# Coordinator.net
KiCad netlist of a schematic drawn in EAGLE
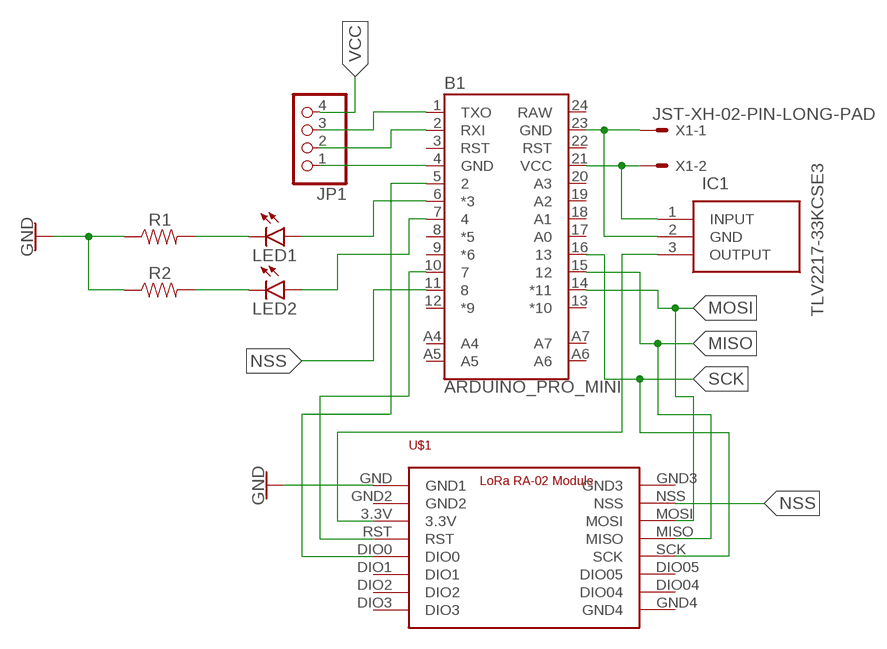
[diagram p0: schematic, sheet 1]

(export (version "E")
  (design (tool "Eeschema 10.0.6"))
  (components
    (comp (ref "B1")
      (value "ARDUINO_PRO_MINI")
      (footprint "eagle-import:ARDUINO_PRO_MINI")
      (libsource (lib "eagle-import") (part "ARDUINO_PRO_MINI"))
    )
    (comp (ref "IC1")
      (value "TLV2217-33KCSE3")
      (footprint "eagle-import:TO254P470X1016X1965-3P")
      (fields (field (name "MOUSER_PART_NUMBER") "595-TLV2217-33KCSE3"))
      (libsource (lib "eagle-import") (part "TLV2217-33KCSE3"))
    )
    (comp (ref "JP1")
      (value "PINHD-1X4")
      (footprint "eagle-import:1X04")
      (libsource (lib "eagle-import") (part "PINHD-1X4"))
    )
    (comp (ref "LED1")
      (value "LEDCHIPLED_0805")
      (footprint "eagle-import:CHIPLED_0805")
      (libsource (lib "eagle-import") (part "LEDCHIPLED_0805"))
    )
    (comp (ref "LED2")
      (value "LEDCHIPLED_0805")
      (footprint "eagle-import:CHIPLED_0805")
      (libsource (lib "eagle-import") (part "LEDCHIPLED_0805"))
    )
    (comp (ref "R1")
      (value "RESISTOR0805")
      (footprint "eagle-import:0805")
      (libsource (lib "eagle-import") (part "RESISTOR0805"))
    )
    (comp (ref "R2")
      (value "RESISTOR0805")
      (footprint "eagle-import:0805")
      (libsource (lib "eagle-import") (part "RESISTOR0805"))
    )
    (comp (ref "U$1")
      (value "LORA_RA-02_MODULE")
      (footprint "eagle-import:LORA_RA-02_MODULE_FOOTPRINT")
      (libsource (lib "eagle-import") (part "LORA_RA-02_MODULE"))
    )
    (comp (ref "X1")
      (value "JST-XH-02-PIN-LONG-PAD")
      (footprint "eagle-import:JST-XH-02-PACKAGE-LONG-PAD")
      (libsource (lib "eagle-import") (part "JST-XH-02-PIN-LONG-PAD"))
    )
  )
  (nets
    (net (code "1") (name "/RAW") (class "Default")
      (node (ref "B1") (pin "24") (pinfunction "RAW_24") (pintype "power_in"))
    )
    (net (code "2") (name "GND") (class "Default")
      (node (ref "R1") (pin "1") (pinfunction "1_1") (pintype "passive"))
      (node (ref "R2") (pin "1") (pinfunction "1_1") (pintype "passive"))
      (node (ref "U$1") (pin "GND") (pinfunction "GND1_GND") (pintype "bidirectional"))
    )
    (net (code "3") (name "MISO") (class "Default")
      (node (ref "B1") (pin "15") (pinfunction "12_15") (pintype "bidirectional"))
      (node (ref "U$1") (pin "MISO") (pinfunction "MISO_MISO") (pintype "bidirectional"))
    )
    (net (code "4") (name "MOSI") (class "Default")
      (node (ref "B1") (pin "14") (pinfunction "*11_14") (pintype "bidirectional"))
      (node (ref "U$1") (pin "MOSI") (pinfunction "MOSI_MOSI") (pintype "bidirectional"))
    )
    (net (code "5") (name "NSS") (class "Default")
      (node (ref "B1") (pin "11") (pinfunction "8_11") (pintype "bidirectional"))
      (node (ref "U$1") (pin "NSS") (pinfunction "NSS_NSS") (pintype "bidirectional"))
    )
    (net (code "6") (name "Net-(B1-*3)") (class "Default")
      (node (ref "B1") (pin "6") (pinfunction "*3_6") (pintype "bidirectional"))
      (node (ref "LED1") (pin "A") (pinfunction "A_A") (pintype "passive"))
    )
    (net (code "7") (name "Net-(B1-2)") (class "Default")
      (node (ref "B1") (pin "5") (pinfunction "2_5") (pintype "bidirectional"))
      (node (ref "U$1") (pin "DIO0") (pinfunction "DIO0_DIO0") (pintype "bidirectional"))
    )
    (net (code "8") (name "Net-(B1-4)") (class "Default")
      (node (ref "B1") (pin "7") (pinfunction "4_7") (pintype "bidirectional"))
      (node (ref "LED2") (pin "A") (pinfunction "A_A") (pintype "passive"))
    )
    (net (code "9") (name "Net-(B1-7)") (class "Default")
      (node (ref "B1") (pin "10") (pinfunction "7_10") (pintype "bidirectional"))
      (node (ref "U$1") (pin "RST") (pinfunction "RST_RST") (pintype "bidirectional"))
    )
    (net (code "10") (name "Net-(B1-GND-Pad4)") (class "Default")
      (node (ref "B1") (pin "4") (pinfunction "GND_4") (pintype "power_in"))
      (node (ref "JP1") (pin "1") (pinfunction "1_1") (pintype "passive"))
    )
    (net (code "11") (name "Net-(B1-RXI)") (class "Default")
      (node (ref "B1") (pin "2") (pinfunction "RXI_2") (pintype "bidirectional"))
      (node (ref "JP1") (pin "2") (pinfunction "2_2") (pintype "passive"))
    )
    (net (code "12") (name "Net-(B1-TXO)") (class "Default")
      (node (ref "B1") (pin "1") (pinfunction "TXO_1") (pintype "bidirectional"))
      (node (ref "JP1") (pin "3") (pinfunction "3_3") (pintype "passive"))
    )
    (net (code "13") (name "Net-(B1-VCC)") (class "Default")
      (node (ref "B1") (pin "21") (pinfunction "VCC_21") (pintype "power_in"))
      (node (ref "IC1") (pin "1") (pinfunction "INPUT_1") (pintype "bidirectional"))
      (node (ref "X1") (pin "2") (pinfunction "S_2") (pintype "passive"))
    )
    (net (code "14") (name "Net-(IC1-GND)") (class "Default")
      (node (ref "B1") (pin "23") (pinfunction "GND_23") (pintype "power_in"))
      (node (ref "IC1") (pin "2") (pinfunction "GND_2") (pintype "bidirectional"))
      (node (ref "X1") (pin "1") (pinfunction "S_1") (pintype "passive"))
    )
    (net (code "15") (name "Net-(IC1-OUTPUT)") (class "Default")
      (node (ref "IC1") (pin "3") (pinfunction "OUTPUT_3") (pintype "bidirectional"))
      (node (ref "U$1") (pin "3.3V") (pinfunction "3.3V_3.3V") (pintype "bidirectional"))
    )
    (net (code "16") (name "Net-(LED1-PadC)") (class "Default")
      (node (ref "LED1") (pin "C") (pinfunction "C_C") (pintype "passive"))
      (node (ref "R1") (pin "2") (pinfunction "2_2") (pintype "passive"))
    )
    (net (code "17") (name "Net-(LED2-PadC)") (class "Default")
      (node (ref "LED2") (pin "C") (pinfunction "C_C") (pintype "passive"))
      (node (ref "R2") (pin "2") (pinfunction "2_2") (pintype "passive"))
    )
    (net (code "18") (name "SCK") (class "Default")
      (node (ref "B1") (pin "16") (pinfunction "13_16") (pintype "bidirectional"))
      (node (ref "U$1") (pin "SCK") (pinfunction "SCK_SCK") (pintype "bidirectional"))
    )
    (net (code "19") (name "VCC") (class "Default")
      (node (ref "JP1") (pin "4") (pinfunction "4_4") (pintype "passive"))
    )
    (net (code "20") (name "unconnected-(B1-*5-Pad8)") (class "Default")
      (node (ref "B1") (pin "8") (pinfunction "*5_8") (pintype "bidirectional"))
    )
    (net (code "21") (name "unconnected-(B1-*6-Pad9)") (class "Default")
      (node (ref "B1") (pin "9") (pinfunction "*6_9") (pintype "bidirectional"))
    )
    (net (code "22") (name "unconnected-(B1-*9-Pad12)") (class "Default")
      (node (ref "B1") (pin "12") (pinfunction "*9_12") (pintype "bidirectional"))
    )
    (net (code "23") (name "unconnected-(B1-*10-Pad13)") (class "Default")
      (node (ref "B1") (pin "13") (pinfunction "*10_13") (pintype "bidirectional"))
    )
    (net (code "24") (name "unconnected-(B1-A0-Pad17)") (class "Default")
      (node (ref "B1") (pin "17") (pinfunction "A0_17") (pintype "bidirectional"))
    )
    (net (code "25") (name "unconnected-(B1-A1-Pad18)") (class "Default")
      (node (ref "B1") (pin "18") (pinfunction "A1_18") (pintype "bidirectional"))
    )
    (net (code "26") (name "unconnected-(B1-A2-Pad19)") (class "Default")
      (node (ref "B1") (pin "19") (pinfunction "A2_19") (pintype "bidirectional"))
    )
    (net (code "27") (name "unconnected-(B1-A3-Pad20)") (class "Default")
      (node (ref "B1") (pin "20") (pinfunction "A3_20") (pintype "bidirectional"))
    )
    (net (code "28") (name "unconnected-(B1-PadA4)") (class "Default")
      (node (ref "B1") (pin "A4") (pinfunction "A4_A4") (pintype "bidirectional"))
    )
    (net (code "29") (name "unconnected-(B1-PadA5)") (class "Default")
      (node (ref "B1") (pin "A5") (pinfunction "A5_A5") (pintype "bidirectional"))
    )
    (net (code "30") (name "unconnected-(B1-PadA6)") (class "Default")
      (node (ref "B1") (pin "A6") (pinfunction "A6_A6") (pintype "bidirectional"))
    )
    (net (code "31") (name "unconnected-(B1-PadA7)") (class "Default")
      (node (ref "B1") (pin "A7") (pinfunction "A7_A7") (pintype "bidirectional"))
    )
    (net (code "32") (name "unconnected-(B1-RST-Pad3)") (class "Default")
      (node (ref "B1") (pin "3") (pinfunction "RST_3") (pintype "bidirectional"))
    )
    (net (code "33") (name "unconnected-(B1-RST-Pad22)") (class "Default")
      (node (ref "B1") (pin "22") (pinfunction "RST_22") (pintype "bidirectional"))
    )
    (net (code "34") (name "unconnected-(U$1-PadDIO1)") (class "Default")
      (node (ref "U$1") (pin "DIO1") (pinfunction "DIO1_DIO1") (pintype "bidirectional"))
    )
    (net (code "35") (name "unconnected-(U$1-PadDIO2)") (class "Default")
      (node (ref "U$1") (pin "DIO2") (pinfunction "DIO2_DIO2") (pintype "bidirectional"))
    )
    (net (code "36") (name "unconnected-(U$1-PadDIO3)") (class "Default")
      (node (ref "U$1") (pin "DIO3") (pinfunction "DIO3_DIO3") (pintype "bidirectional"))
    )
    (net (code "37") (name "unconnected-(U$1-PadDIO04)") (class "Default")
      (node (ref "U$1") (pin "DIO04") (pinfunction "DIO04_DIO04") (pintype "bidirectional"))
    )
    (net (code "38") (name "unconnected-(U$1-PadDIO05)") (class "Default")
      (node (ref "U$1") (pin "DIO05") (pinfunction "DIO05_DIO05") (pintype "bidirectional"))
    )
    (net (code "39") (name "unconnected-(U$1-PadGND2)") (class "Default")
      (node (ref "U$1") (pin "GND2") (pinfunction "GND2_GND2") (pintype "bidirectional"))
    )
    (net (code "40") (name "unconnected-(U$1-PadGND3)") (class "Default")
      (node (ref "U$1") (pin "GND3") (pinfunction "GND3_GND3") (pintype "bidirectional"))
    )
    (net (code "41") (name "unconnected-(U$1-PadGND4)") (class "Default")
      (node (ref "U$1") (pin "GND4") (pinfunction "GND4_GND4") (pintype "bidirectional"))
    )
  )
)
